# EE445L_Lab_7_Starter.net
KiCad netlist of a schematic drawn in EAGLE
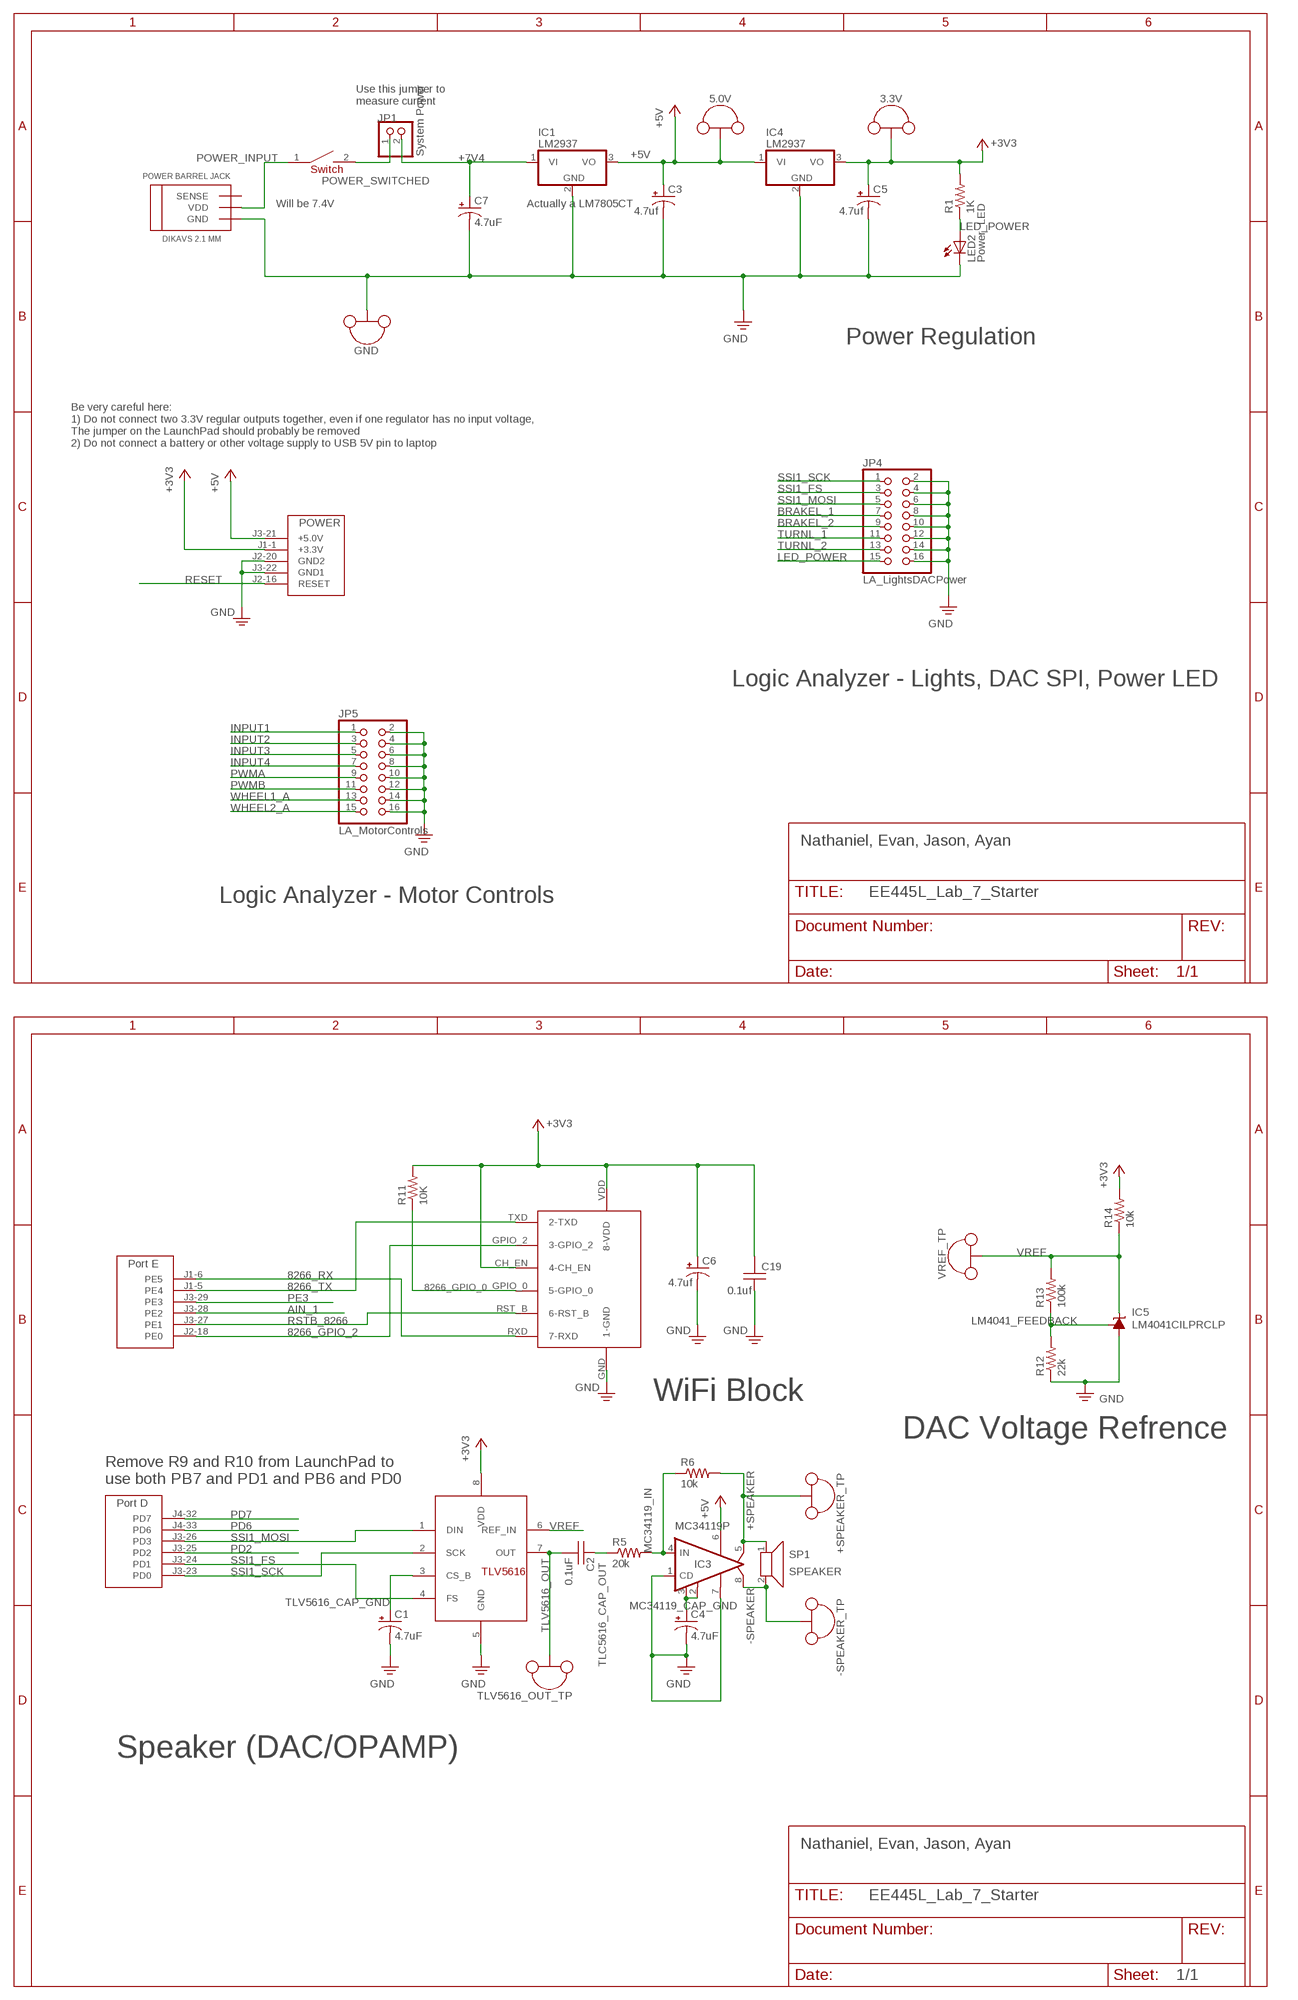
[diagram p0: schematic, sheet 1, part 1 of 2]
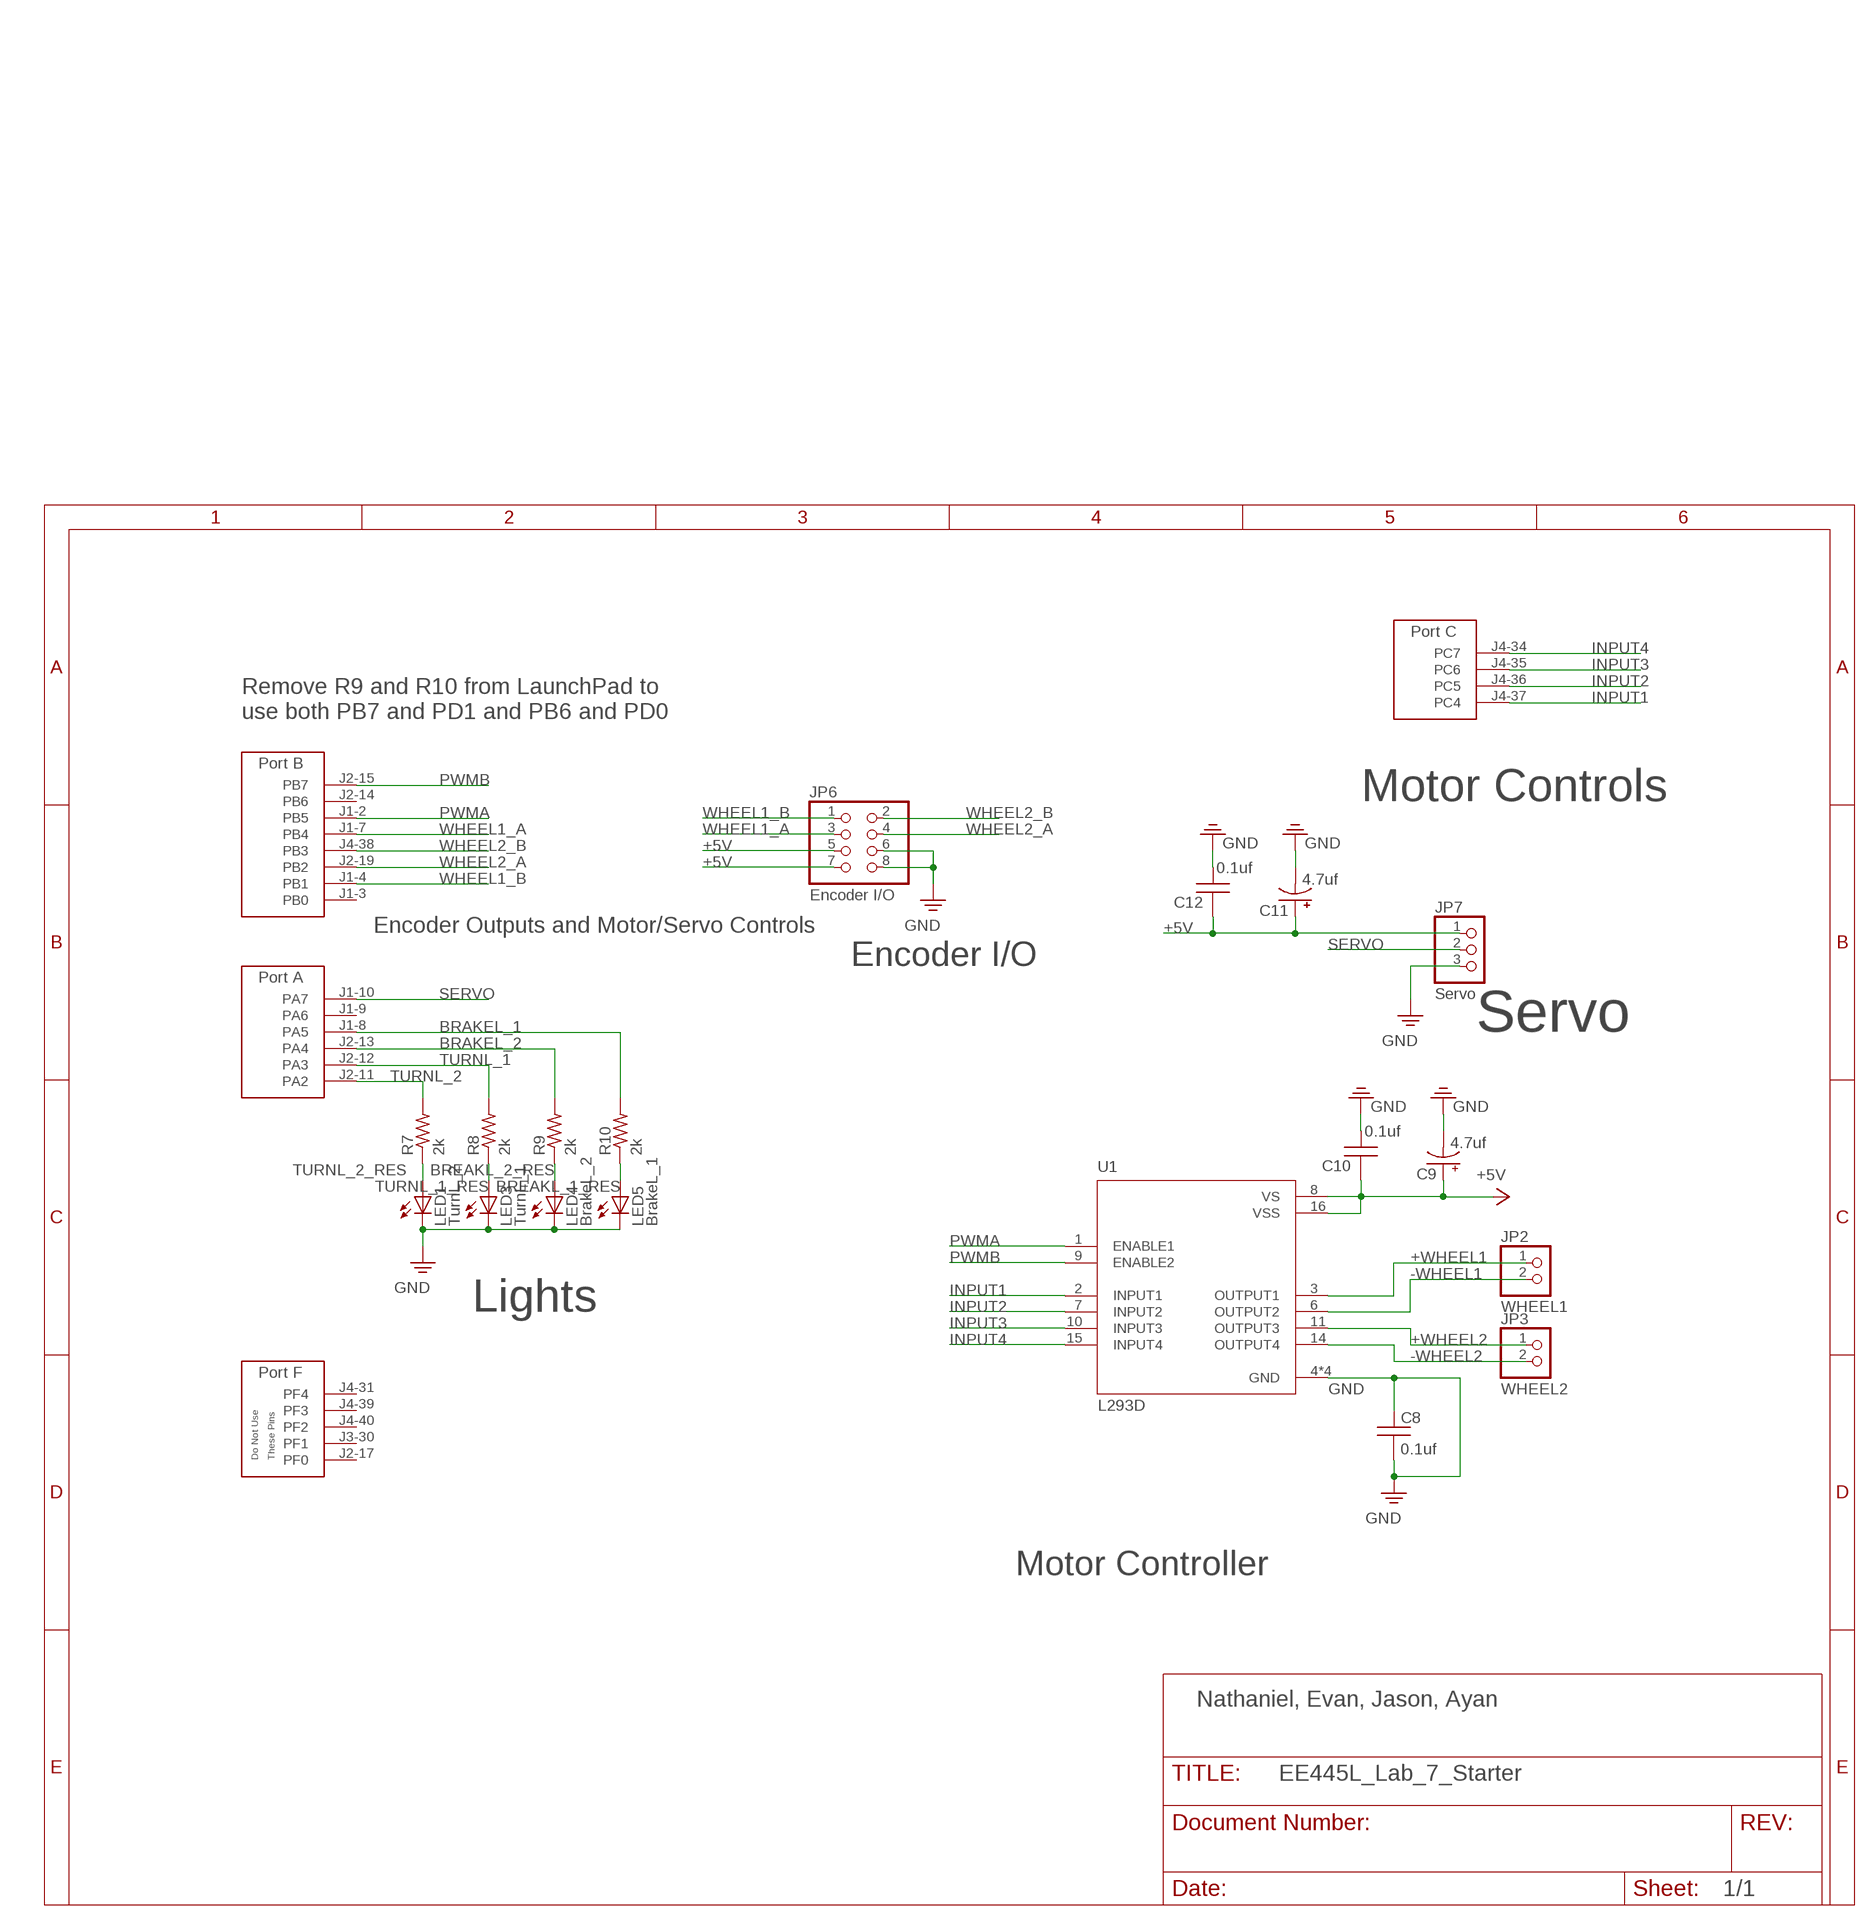
[diagram p1: schematic, sheet 1, part 2 of 2]

(export (version "E")
  (design (tool "Eeschema 10.0.6"))
  (components
    (comp (ref "+SPEAKER_TP")
      (value "TP_LOOP")
      (footprint "eagle-import:TP_LOOP")
      (libsource (lib "eagle-import") (part "TP_LOOP"))
    )
    (comp (ref "-SPEAKER_TP")
      (value "TP_LOOP")
      (footprint "eagle-import:TP_LOOP")
      (libsource (lib "eagle-import") (part "TP_LOOP"))
    )
    (comp (ref "3.3V")
      (value "TP_LOOP")
      (footprint "eagle-import:TP_LOOP")
      (libsource (lib "eagle-import") (part "TP_LOOP"))
    )
    (comp (ref "5.0V")
      (value "TP_LOOP")
      (footprint "eagle-import:TP_LOOP")
      (libsource (lib "eagle-import") (part "TP_LOOP"))
    )
    (comp (ref "C1")
      (value "4.7uF")
      (footprint "eagle-import:CAP200MILPOLARIZED")
      (libsource (lib "eagle-import") (part "CAPACITOR_POLARIZEDE5-6"))
    )
    (comp (ref "C2")
      (value "0.1uF")
      (footprint "eagle-import:CAP100MIL")
      (libsource (lib "eagle-import") (part "CAPACITOR025-024X044"))
    )
    (comp (ref "C3")
      (value "4.7uf")
      (footprint "eagle-import:CAP200MILPOLARIZED")
      (libsource (lib "eagle-import") (part "CAPACITOR_POLARIZEDE5-6"))
    )
    (comp (ref "C4")
      (value "4.7uF")
      (footprint "eagle-import:CAP200MILPOLARIZED")
      (libsource (lib "eagle-import") (part "CAPACITOR_POLARIZEDE5-6"))
    )
    (comp (ref "C5")
      (value "4.7uf")
      (footprint "eagle-import:CAP200MILPOLARIZED")
      (libsource (lib "eagle-import") (part "CAPACITOR_POLARIZEDE5-6"))
    )
    (comp (ref "C6")
      (value "4.7uf")
      (footprint "eagle-import:CAP200MILPOLARIZED")
      (libsource (lib "eagle-import") (part "CAPACITOR_POLARIZEDE5-6"))
    )
    (comp (ref "C7")
      (value "4.7uF")
      (footprint "eagle-import:CAP200MILPOLARIZED")
      (libsource (lib "eagle-import") (part "CAPACITOR_POLARIZEDE5-6"))
    )
    (comp (ref "C8")
      (value "0.1uf")
      (footprint "eagle-import:CAP100MIL")
      (libsource (lib "eagle-import") (part "CAPACITOR025-024X044"))
    )
    (comp (ref "C9")
      (value "4.7uf")
      (footprint "eagle-import:CAP200MILPOLARIZED")
      (libsource (lib "eagle-import") (part "CAPACITOR_POLARIZEDE5-6"))
    )
    (comp (ref "C10")
      (value "0.1uf")
      (footprint "eagle-import:CAP200MIL")
      (libsource (lib "eagle-import") (part "CAPACITOR050-024X044"))
    )
    (comp (ref "C11")
      (value "4.7uf")
      (footprint "eagle-import:CAP200MILPOLARIZED")
      (libsource (lib "eagle-import") (part "CAPACITOR_POLARIZEDE5-6"))
    )
    (comp (ref "C12")
      (value "0.1uf")
      (footprint "eagle-import:CAP200MIL")
      (libsource (lib "eagle-import") (part "CAPACITOR050-024X044"))
    )
    (comp (ref "C19")
      (value "0.1uf")
      (footprint "eagle-import:CAP200MIL")
      (libsource (lib "eagle-import") (part "CAPACITOR050-024X044"))
    )
    (comp (ref "GND")
      (value "TP_LOOP")
      (footprint "eagle-import:TP_LOOP")
      (libsource (lib "eagle-import") (part "TP_LOOP"))
    )
    (comp (ref "IC1")
      (value "LM2937")
      (footprint "eagle-import:TO220")
      (libsource (lib "eagle-import") (part "LM2937"))
    )
    (comp (ref "IC3")
      (value "MC34119P")
      (footprint "eagle-import:DIL08")
      (libsource (lib "eagle-import") (part "MC34119P"))
    )
    (comp (ref "IC4")
      (value "LM2937")
      (footprint "eagle-import:TO220")
      (libsource (lib "eagle-import") (part "LM2937"))
    )
    (comp (ref "IC5")
      (value "LM4041CILPRCLP")
      (footprint "eagle-import:LP_O-PBCY-W3")
      (fields (field (name "MPN") "LM4041CILP"))
      (libsource (lib "eagle-import") (part "LM4041CILPRLPC"))
    )
    (comp (ref "JP1")
      (value "System Power")
      (footprint "eagle-import:1X02")
      (libsource (lib "eagle-import") (part "PINHD-1X2"))
    )
    (comp (ref "JP2")
      (value "WHEEL1")
      (footprint "eagle-import:1X02")
      (libsource (lib "eagle-import") (part "PINHD-1X2"))
    )
    (comp (ref "JP3")
      (value "WHEEL2")
      (footprint "eagle-import:1X02")
      (libsource (lib "eagle-import") (part "PINHD-1X2"))
    )
    (comp (ref "JP4")
      (value "LA_LightsDACPower")
      (footprint "eagle-import:2X08")
      (libsource (lib "eagle-import") (part "PINHD-2X8"))
    )
    (comp (ref "JP5")
      (value "LA_MotorControls")
      (footprint "eagle-import:2X08")
      (libsource (lib "eagle-import") (part "PINHD-2X8"))
    )
    (comp (ref "JP6")
      (value "Encoder I/O")
      (footprint "eagle-import:2X04")
      (libsource (lib "eagle-import") (part "PINHD-2X4"))
    )
    (comp (ref "JP7")
      (value "Servo")
      (footprint "eagle-import:1X03")
      (libsource (lib "eagle-import") (part "PINHD-1X3"))
    )
    (comp (ref "LED1")
      (value "TurnL_2")
      (footprint "eagle-import:LED3MM")
      (libsource (lib "eagle-import") (part "LED3MM"))
    )
    (comp (ref "LED2")
      (value "Power_LED")
      (footprint "eagle-import:LED3MM")
      (libsource (lib "eagle-import") (part "LED3MM"))
    )
    (comp (ref "LED3")
      (value "TurnL_1")
      (footprint "eagle-import:LED3MM")
      (libsource (lib "eagle-import") (part "LED3MM"))
    )
    (comp (ref "LED4")
      (value "BrakeL_2")
      (footprint "eagle-import:LED3MM")
      (libsource (lib "eagle-import") (part "LED3MM"))
    )
    (comp (ref "LED5")
      (value "BrakeL_1")
      (footprint "eagle-import:LED3MM")
      (libsource (lib "eagle-import") (part "LED3MM"))
    )
    (comp (ref "R1")
      (value "1K")
      (footprint "eagle-import:RES200MIL")
      (libsource (lib "eagle-import") (part "RESISTOR0204/5"))
    )
    (comp (ref "R5")
      (value "20k")
      (footprint "eagle-import:RES200MIL")
      (libsource (lib "eagle-import") (part "RESISTOR0204/5"))
    )
    (comp (ref "R6")
      (value "10k")
      (footprint "eagle-import:RES200MIL")
      (libsource (lib "eagle-import") (part "RESISTOR0204/5"))
    )
    (comp (ref "R7")
      (value "2k")
      (footprint "eagle-import:RES200MIL")
      (libsource (lib "eagle-import") (part "RESISTOR0204/5"))
    )
    (comp (ref "R8")
      (value "2k")
      (footprint "eagle-import:RES200MIL")
      (libsource (lib "eagle-import") (part "RESISTOR0204/5"))
    )
    (comp (ref "R9")
      (value "2k")
      (footprint "eagle-import:RES200MIL")
      (libsource (lib "eagle-import") (part "RESISTOR0204/5"))
    )
    (comp (ref "R10")
      (value "2k")
      (footprint "eagle-import:RES200MIL")
      (libsource (lib "eagle-import") (part "RESISTOR0204/5"))
    )
    (comp (ref "R11")
      (value "10K")
      (footprint "eagle-import:RES300MIL")
      (libsource (lib "eagle-import") (part "RESISTOR0204/7"))
    )
    (comp (ref "R12")
      (value "22k")
      (footprint "eagle-import:RES300MIL")
      (libsource (lib "eagle-import") (part "RESISTOR0204/7"))
    )
    (comp (ref "R13")
      (value "100k")
      (footprint "eagle-import:RES300MIL")
      (libsource (lib "eagle-import") (part "RESISTOR0204/7"))
    )
    (comp (ref "R14")
      (value "10k")
      (footprint "eagle-import:RES300MIL")
      (libsource (lib "eagle-import") (part "RESISTOR0204/7"))
    )
    (comp (ref "SP1")
      (value "SPEAKER")
      (footprint "eagle-import:1X02")
      (libsource (lib "eagle-import") (part "SPEAKER"))
    )
    (comp (ref "TLV5616_OUT_TP")
      (value "TP_LOOP")
      (footprint "eagle-import:TP_LOOP")
      (libsource (lib "eagle-import") (part "TP_LOOP"))
    )
    (comp (ref "U$1")
      (value "TLV5616")
      (footprint "eagle-import:DIL08")
      (libsource (lib "eagle-import") (part "TLV5616"))
    )
    (comp (ref "U$2")
      (value "TM4C_BP")
      (footprint "eagle-import:TM4C_BOOSTER_PACK")
      (libsource (lib "eagle-import") (part "TM4C_BP"))
    )
    (comp (ref "U$3")
      (value "ESP_8266")
      (footprint "eagle-import:ESP8266")
      (libsource (lib "eagle-import") (part "ESP_8266"))
    )
    (comp (ref "U$4")
      (value "2.1MM_BARREL_JACK")
      (footprint "eagle-import:2.1M_BARREL_JACK")
      (libsource (lib "eagle-import") (part "2.1MM_BARREL_JACK"))
    )
    (comp (ref "U$6")
      (value "SW_POWER_100MIL")
      (footprint "eagle-import:SW_POWER")
      (libsource (lib "eagle-import") (part "SW_POWER_100MIL"))
    )
    (comp (ref "U1")
      (value "L293D")
      (footprint "eagle-import:DIP880W50P254L2000H510Q16")
      (fields (field (name "MF") "STMicroelectronics"))
      (libsource (lib "eagle-import") (part "L293D"))
    )
    (comp (ref "VREF_TP")
      (value "TP_LOOP")
      (footprint "eagle-import:TP_LOOP")
      (libsource (lib "eagle-import") (part "TP_LOOP"))
    )
  )
  (nets
    (net (code "1") (name "+3V3") (class "Default")
      (node (ref "3.3V") (pin "P$1") (pinfunction "TP_P$1") (pintype "bidirectional"))
      (node (ref "3.3V") (pin "P$2") (pinfunction "TP_P$2") (pintype "bidirectional"))
      (node (ref "C19") (pin "2") (pinfunction "2_2") (pintype "passive"))
      (node (ref "C5") (pin "+") (pinfunction "+_+") (pintype "passive"))
      (node (ref "C6") (pin "+") (pinfunction "+_+") (pintype "passive"))
      (node (ref "IC4") (pin "3") (pinfunction "VO_3") (pintype "passive"))
      (node (ref "R1") (pin "2") (pinfunction "2_2") (pintype "passive"))
      (node (ref "R11") (pin "2") (pinfunction "2_2") (pintype "passive"))
      (node (ref "R14") (pin "2") (pinfunction "2_2") (pintype "passive"))
      (node (ref "U$1") (pin "8") (pinfunction "VDD_8") (pintype "bidirectional"))
      (node (ref "U$2") (pin "J1-1") (pinfunction "+3.3V_J1-1") (pintype "bidirectional"))
      (node (ref "U$3") (pin "CH_EN") (pinfunction "4-CH_EN_CH_EN") (pintype "bidirectional"))
      (node (ref "U$3") (pin "VDD") (pinfunction "8-VDD_VDD") (pintype "bidirectional"))
    )
    (net (code "2") (name "+5V") (class "Default")
      (node (ref "5.0V") (pin "P$1") (pinfunction "TP_P$1") (pintype "bidirectional"))
      (node (ref "5.0V") (pin "P$2") (pinfunction "TP_P$2") (pintype "bidirectional"))
      (node (ref "C10") (pin "2") (pinfunction "2_2") (pintype "passive"))
      (node (ref "C11") (pin "+") (pinfunction "+_+") (pintype "passive"))
      (node (ref "C12") (pin "2") (pinfunction "2_2") (pintype "passive"))
      (node (ref "C3") (pin "+") (pinfunction "+_+") (pintype "passive"))
      (node (ref "C9") (pin "+") (pinfunction "+_+") (pintype "passive"))
      (node (ref "IC1") (pin "3") (pinfunction "VO_3") (pintype "passive"))
      (node (ref "IC3") (pin "6") (pinfunction "VCC_6") (pintype "power_in"))
      (node (ref "IC4") (pin "1") (pinfunction "VI_1") (pintype "input"))
      (node (ref "JP6") (pin "5") (pinfunction "5_5") (pintype "passive"))
      (node (ref "JP6") (pin "7") (pinfunction "7_7") (pintype "passive"))
      (node (ref "JP7") (pin "1") (pinfunction "1_1") (pintype "passive"))
      (node (ref "U$2") (pin "J3-21") (pinfunction "+5.0V_J3-21") (pintype "bidirectional"))
      (node (ref "U1") (pin "16") (pinfunction "VSS_16") (pintype "power_in"))
      (node (ref "U1") (pin "8") (pinfunction "VS_8") (pintype "power_in"))
    )
    (net (code "3") (name "/+7V4") (class "Default")
      (node (ref "C7") (pin "+") (pinfunction "+_+") (pintype "passive"))
      (node (ref "IC1") (pin "1") (pinfunction "VI_1") (pintype "input"))
      (node (ref "JP1") (pin "2") (pinfunction "2_2") (pintype "passive"))
    )
    (net (code "4") (name "/+SPEAKER") (class "Default")
      (node (ref "+SPEAKER_TP") (pin "P$1") (pinfunction "TP_P$1") (pintype "bidirectional"))
      (node (ref "+SPEAKER_TP") (pin "P$2") (pinfunction "TP_P$2") (pintype "bidirectional"))
      (node (ref "IC3") (pin "5") (pinfunction "VO1_5") (pintype "output"))
      (node (ref "R6") (pin "2") (pinfunction "2_2") (pintype "passive"))
      (node (ref "SP1") (pin "1") (pinfunction "1_1") (pintype "passive"))
    )
    (net (code "5") (name "/+WHEEL1") (class "Default")
      (node (ref "JP2") (pin "1") (pinfunction "1_1") (pintype "passive"))
      (node (ref "U1") (pin "3") (pinfunction "OUTPUT1_3") (pintype "output"))
    )
    (net (code "6") (name "/+WHEEL2") (class "Default")
      (node (ref "JP3") (pin "1") (pinfunction "1_1") (pintype "passive"))
      (node (ref "U1") (pin "11") (pinfunction "OUTPUT3_11") (pintype "output"))
    )
    (net (code "7") (name "/-SPEAKER") (class "Default")
      (node (ref "-SPEAKER_TP") (pin "P$1") (pinfunction "TP_P$1") (pintype "bidirectional"))
      (node (ref "-SPEAKER_TP") (pin "P$2") (pinfunction "TP_P$2") (pintype "bidirectional"))
      (node (ref "IC3") (pin "8") (pinfunction "VO2_8") (pintype "output"))
      (node (ref "SP1") (pin "2") (pinfunction "2_2") (pintype "passive"))
    )
    (net (code "8") (name "/-WHEEL1") (class "Default")
      (node (ref "JP2") (pin "2") (pinfunction "2_2") (pintype "passive"))
      (node (ref "U1") (pin "6") (pinfunction "OUTPUT2_6") (pintype "output"))
    )
    (net (code "9") (name "/-WHEEL2") (class "Default")
      (node (ref "JP3") (pin "2") (pinfunction "2_2") (pintype "passive"))
      (node (ref "U1") (pin "14") (pinfunction "OUTPUT4_14") (pintype "output"))
    )
    (net (code "10") (name "/8266_GPIO_0") (class "Default")
      (node (ref "R11") (pin "1") (pinfunction "1_1") (pintype "passive"))
      (node (ref "U$3") (pin "GPIO_0") (pinfunction "5-GPIO_0_GPIO_0") (pintype "bidirectional"))
    )
    (net (code "11") (name "/8266_GPIO_2") (class "Default")
      (node (ref "U$2") (pin "J2-18") (pinfunction "PE0_J2-18") (pintype "bidirectional"))
      (node (ref "U$3") (pin "GPIO_2") (pinfunction "3-GPIO_2_GPIO_2") (pintype "bidirectional"))
    )
    (net (code "12") (name "/8266_RX") (class "Default")
      (node (ref "U$2") (pin "J1-6") (pinfunction "PE5_J1-6") (pintype "bidirectional"))
      (node (ref "U$3") (pin "RXD") (pinfunction "7-RXD_RXD") (pintype "bidirectional"))
    )
    (net (code "13") (name "/8266_TX") (class "Default")
      (node (ref "U$2") (pin "J1-5") (pinfunction "PE4_J1-5") (pintype "bidirectional"))
      (node (ref "U$3") (pin "TXD") (pinfunction "2-TXD_TXD") (pintype "bidirectional"))
    )
    (net (code "14") (name "/AIN_1") (class "Default")
      (node (ref "U$2") (pin "J3-28") (pinfunction "PE2_J3-28") (pintype "bidirectional"))
    )
    (net (code "15") (name "/BRAKEL_1") (class "Default")
      (node (ref "JP4") (pin "7") (pinfunction "7_7") (pintype "passive"))
      (node (ref "R10") (pin "2") (pinfunction "2_2") (pintype "passive"))
      (node (ref "U$2") (pin "J1-8") (pinfunction "PA5_J1-8") (pintype "bidirectional"))
    )
    (net (code "16") (name "/BRAKEL_2") (class "Default")
      (node (ref "JP4") (pin "9") (pinfunction "9_9") (pintype "passive"))
      (node (ref "R9") (pin "2") (pinfunction "2_2") (pintype "passive"))
      (node (ref "U$2") (pin "J2-13") (pinfunction "PA4_J2-13") (pintype "bidirectional"))
    )
    (net (code "17") (name "/BREAKL_1_RES") (class "Default")
      (node (ref "LED5") (pin "A") (pinfunction "A_A") (pintype "passive"))
      (node (ref "R10") (pin "1") (pinfunction "1_1") (pintype "passive"))
    )
    (net (code "18") (name "/BREAKL_2_RES") (class "Default")
      (node (ref "LED4") (pin "A") (pinfunction "A_A") (pintype "passive"))
      (node (ref "R9") (pin "1") (pinfunction "1_1") (pintype "passive"))
    )
    (net (code "19") (name "/INPUT1") (class "Default")
      (node (ref "JP5") (pin "1") (pinfunction "1_1") (pintype "passive"))
      (node (ref "U$2") (pin "J4-37") (pinfunction "PC4_J4-37") (pintype "bidirectional"))
      (node (ref "U1") (pin "2") (pinfunction "INPUT1_2") (pintype "input"))
    )
    (net (code "20") (name "/INPUT2") (class "Default")
      (node (ref "JP5") (pin "3") (pinfunction "3_3") (pintype "passive"))
      (node (ref "U$2") (pin "J4-36") (pinfunction "PC5_J4-36") (pintype "bidirectional"))
      (node (ref "U1") (pin "7") (pinfunction "INPUT2_7") (pintype "input"))
    )
    (net (code "21") (name "/INPUT3") (class "Default")
      (node (ref "JP5") (pin "5") (pinfunction "5_5") (pintype "passive"))
      (node (ref "U$2") (pin "J4-35") (pinfunction "PC6_J4-35") (pintype "bidirectional"))
      (node (ref "U1") (pin "10") (pinfunction "INPUT3_10") (pintype "input"))
    )
    (net (code "22") (name "/INPUT4") (class "Default")
      (node (ref "JP5") (pin "7") (pinfunction "7_7") (pintype "passive"))
      (node (ref "U$2") (pin "J4-34") (pinfunction "PC7_J4-34") (pintype "bidirectional"))
      (node (ref "U1") (pin "15") (pinfunction "INPUT4_15") (pintype "input"))
    )
    (net (code "23") (name "/LED_POWER") (class "Default")
      (node (ref "JP4") (pin "15") (pinfunction "15_15") (pintype "passive"))
      (node (ref "LED2") (pin "A") (pinfunction "A_A") (pintype "passive"))
      (node (ref "R1") (pin "1") (pinfunction "1_1") (pintype "passive"))
    )
    (net (code "24") (name "/LM4041_FEEDBACK") (class "Default")
      (node (ref "IC5") (pin "1") (pinfunction "FB_1") (pintype "passive"))
      (node (ref "R12") (pin "2") (pinfunction "2_2") (pintype "passive"))
      (node (ref "R13") (pin "1") (pinfunction "1_1") (pintype "passive"))
    )
    (net (code "25") (name "/MC34119_CAP_GND") (class "Default")
      (node (ref "C4") (pin "+") (pinfunction "+_+") (pintype "passive"))
      (node (ref "IC3") (pin "2") (pinfunction "FC2_2") (pintype "passive"))
      (node (ref "IC3") (pin "3") (pinfunction "FC1_3") (pintype "passive"))
    )
    (net (code "26") (name "/MC34119_IN") (class "Default")
      (node (ref "IC3") (pin "4") (pinfunction "IN_4") (pintype "input"))
      (node (ref "R5") (pin "2") (pinfunction "2_2") (pintype "passive"))
      (node (ref "R6") (pin "1") (pinfunction "1_1") (pintype "passive"))
    )
    (net (code "27") (name "/PD2") (class "Default")
      (node (ref "U$2") (pin "J3-25") (pinfunction "PD2_J3-25") (pintype "bidirectional"))
    )
    (net (code "28") (name "/PD6") (class "Default")
      (node (ref "U$2") (pin "J4-33") (pinfunction "PD6_J4-33") (pintype "bidirectional"))
    )
    (net (code "29") (name "/PD7") (class "Default")
      (node (ref "U$2") (pin "J4-32") (pinfunction "PD7_J4-32") (pintype "bidirectional"))
    )
    (net (code "30") (name "/PE3") (class "Default")
      (node (ref "U$2") (pin "J3-29") (pinfunction "PE3_J3-29") (pintype "bidirectional"))
    )
    (net (code "31") (name "/POWER_INPUT") (class "Default")
      (node (ref "U$4") (pin "VDD") (pinfunction "VDD_VDD") (pintype "bidirectional"))
      (node (ref "U$6") (pin "1") (pinfunction "P$1_1") (pintype "bidirectional"))
    )
    (net (code "32") (name "/POWER_SWITCHED") (class "Default")
      (node (ref "JP1") (pin "1") (pinfunction "1_1") (pintype "passive"))
      (node (ref "U$6") (pin "2") (pinfunction "P$2_2") (pintype "bidirectional"))
    )
    (net (code "33") (name "/PWMA") (class "Default")
      (node (ref "JP5") (pin "9") (pinfunction "9_9") (pintype "passive"))
      (node (ref "U$2") (pin "J1-2") (pinfunction "PB5_J1-2") (pintype "bidirectional"))
      (node (ref "U1") (pin "1") (pinfunction "ENABLE1_1") (pintype "input"))
    )
    (net (code "34") (name "/PWMB") (class "Default")
      (node (ref "JP5") (pin "11") (pinfunction "11_11") (pintype "passive"))
      (node (ref "U$2") (pin "J2-15") (pinfunction "PB7_J2-15") (pintype "bidirectional"))
      (node (ref "U1") (pin "9") (pinfunction "ENABLE2_9") (pintype "input"))
    )
    (net (code "35") (name "/RESET") (class "Default")
      (node (ref "U$2") (pin "J2-16") (pinfunction "RESET_J2-16") (pintype "bidirectional"))
    )
    (net (code "36") (name "/RSTB_8266") (class "Default")
      (node (ref "U$2") (pin "J3-27") (pinfunction "PE1_J3-27") (pintype "bidirectional"))
      (node (ref "U$3") (pin "RST_B") (pinfunction "6-RST_B_RST_B") (pintype "bidirectional"))
    )
    (net (code "37") (name "/SERVO") (class "Default")
      (node (ref "JP7") (pin "2") (pinfunction "2_2") (pintype "passive"))
      (node (ref "U$2") (pin "J1-10") (pinfunction "PA7_J1-10") (pintype "bidirectional"))
    )
    (net (code "38") (name "/SSI1_FS") (class "Default")
      (node (ref "JP4") (pin "3") (pinfunction "3_3") (pintype "passive"))
      (node (ref "U$1") (pin "4") (pinfunction "FS_4") (pintype "bidirectional"))
      (node (ref "U$2") (pin "J3-24") (pinfunction "PD1_J3-24") (pintype "bidirectional"))
    )
    (net (code "39") (name "/SSI1_MOSI") (class "Default")
      (node (ref "JP4") (pin "5") (pinfunction "5_5") (pintype "passive"))
      (node (ref "U$1") (pin "1") (pinfunction "DIN_1") (pintype "bidirectional"))
      (node (ref "U$2") (pin "J3-26") (pinfunction "PD3_J3-26") (pintype "bidirectional"))
    )
    (net (code "40") (name "/SSI1_SCK") (class "Default")
      (node (ref "JP4") (pin "1") (pinfunction "1_1") (pintype "passive"))
      (node (ref "U$1") (pin "2") (pinfunction "SCK_2") (pintype "bidirectional"))
      (node (ref "U$2") (pin "J3-23") (pinfunction "PD0_J3-23") (pintype "bidirectional"))
    )
    (net (code "41") (name "/TLC5616_CAP_OUT") (class "Default")
      (node (ref "C2") (pin "1") (pinfunction "1_1") (pintype "passive"))
      (node (ref "R5") (pin "1") (pinfunction "1_1") (pintype "passive"))
    )
    (net (code "42") (name "/TLV5616_CAP_GND") (class "Default")
      (node (ref "C1") (pin "+") (pinfunction "+_+") (pintype "passive"))
      (node (ref "U$1") (pin "3") (pinfunction "CS_B_3") (pintype "bidirectional"))
    )
    (net (code "43") (name "/TLV5616_OUT") (class "Default")
      (node (ref "C2") (pin "2") (pinfunction "2_2") (pintype "passive"))
      (node (ref "TLV5616_OUT_TP") (pin "P$1") (pinfunction "TP_P$1") (pintype "bidirectional"))
      (node (ref "TLV5616_OUT_TP") (pin "P$2") (pinfunction "TP_P$2") (pintype "bidirectional"))
      (node (ref "U$1") (pin "7") (pinfunction "OUT_7") (pintype "bidirectional"))
    )
    (net (code "44") (name "/TURNL_1") (class "Default")
      (node (ref "JP4") (pin "11") (pinfunction "11_11") (pintype "passive"))
      (node (ref "R8") (pin "2") (pinfunction "2_2") (pintype "passive"))
      (node (ref "U$2") (pin "J2-12") (pinfunction "PA3_J2-12") (pintype "bidirectional"))
    )
    (net (code "45") (name "/TURNL_1_RES") (class "Default")
      (node (ref "LED3") (pin "A") (pinfunction "A_A") (pintype "passive"))
      (node (ref "R8") (pin "1") (pinfunction "1_1") (pintype "passive"))
    )
    (net (code "46") (name "/TURNL_2") (class "Default")
      (node (ref "JP4") (pin "13") (pinfunction "13_13") (pintype "passive"))
      (node (ref "R7") (pin "2") (pinfunction "2_2") (pintype "passive"))
      (node (ref "U$2") (pin "J2-11") (pinfunction "PA2_J2-11") (pintype "bidirectional"))
    )
    (net (code "47") (name "/TURNL_2_RES") (class "Default")
      (node (ref "LED1") (pin "A") (pinfunction "A_A") (pintype "passive"))
      (node (ref "R7") (pin "1") (pinfunction "1_1") (pintype "passive"))
    )
    (net (code "48") (name "/VREF") (class "Default")
      (node (ref "IC5") (pin "2") (pinfunction "C_2") (pintype "passive"))
      (node (ref "R13") (pin "2") (pinfunction "2_2") (pintype "passive"))
      (node (ref "R14") (pin "1") (pinfunction "1_1") (pintype "passive"))
      (node (ref "U$1") (pin "6") (pinfunction "REF_IN_6") (pintype "bidirectional"))
      (node (ref "VREF_TP") (pin "P$1") (pinfunction "TP_P$1") (pintype "bidirectional"))
      (node (ref "VREF_TP") (pin "P$2") (pinfunction "TP_P$2") (pintype "bidirectional"))
    )
    (net (code "49") (name "/WHEEL1_A") (class "Default")
      (node (ref "JP5") (pin "13") (pinfunction "13_13") (pintype "passive"))
      (node (ref "JP6") (pin "3") (pinfunction "3_3") (pintype "passive"))
      (node (ref "U$2") (pin "J1-7") (pinfunction "PB4_J1-7") (pintype "bidirectional"))
    )
    (net (code "50") (name "/WHEEL1_B") (class "Default")
      (node (ref "JP6") (pin "1") (pinfunction "1_1") (pintype "passive"))
      (node (ref "U$2") (pin "J1-4") (pinfunction "PB1_J1-4") (pintype "bidirectional"))
    )
    (net (code "51") (name "/WHEEL2_A") (class "Default")
      (node (ref "JP5") (pin "15") (pinfunction "15_15") (pintype "passive"))
      (node (ref "JP6") (pin "4") (pinfunction "4_4") (pintype "passive"))
      (node (ref "U$2") (pin "J2-19") (pinfunction "PB2_J2-19") (pintype "bidirectional"))
    )
    (net (code "52") (name "/WHEEL2_B") (class "Default")
      (node (ref "JP6") (pin "2") (pinfunction "2_2") (pintype "passive"))
      (node (ref "U$2") (pin "J4-38") (pinfunction "PB3_J4-38") (pintype "bidirectional"))
    )
    (net (code "53") (name "GND") (class "Default")
      (node (ref "C1") (pin "-") (pinfunction "-_-") (pintype "passive"))
      (node (ref "C10") (pin "1") (pinfunction "1_1") (pintype "passive"))
      (node (ref "C11") (pin "-") (pinfunction "-_-") (pintype "passive"))
      (node (ref "C12") (pin "1") (pinfunction "1_1") (pintype "passive"))
      (node (ref "C19") (pin "1") (pinfunction "1_1") (pintype "passive"))
      (node (ref "C3") (pin "-") (pinfunction "-_-") (pintype "passive"))
      (node (ref "C4") (pin "-") (pinfunction "-_-") (pintype "passive"))
      (node (ref "C5") (pin "-") (pinfunction "-_-") (pintype "passive"))
      (node (ref "C6") (pin "-") (pinfunction "-_-") (pintype "passive"))
      (node (ref "C7") (pin "-") (pinfunction "-_-") (pintype "passive"))
      (node (ref "C8") (pin "1") (pinfunction "1_1") (pintype "passive"))
      (node (ref "C8") (pin "2") (pinfunction "2_2") (pintype "passive"))
      (node (ref "C9") (pin "-") (pinfunction "-_-") (pintype "passive"))
      (node (ref "GND") (pin "P$1") (pinfunction "TP_P$1") (pintype "bidirectional"))
      (node (ref "GND") (pin "P$2") (pinfunction "TP_P$2") (pintype "bidirectional"))
      (node (ref "IC1") (pin "2") (pinfunction "GND_2") (pintype "passive"))
      (node (ref "IC3") (pin "1") (pinfunction "CD_1") (pintype "passive"))
      (node (ref "IC3") (pin "7") (pinfunction "GND_7") (pintype "power_in"))
      (node (ref "IC4") (pin "2") (pinfunction "GND_2") (pintype "passive"))
      (node (ref "IC5") (pin "3") (pinfunction "A_3") (pintype "passive"))
      (node (ref "JP4") (pin "10") (pinfunction "10_10") (pintype "passive"))
      (node (ref "JP4") (pin "12") (pinfunction "12_12") (pintype "passive"))
      (node (ref "JP4") (pin "14") (pinfunction "14_14") (pintype "passive"))
      (node (ref "JP4") (pin "16") (pinfunction "16_16") (pintype "passive"))
      (node (ref "JP4") (pin "2") (pinfunction "2_2") (pintype "passive"))
      (node (ref "JP4") (pin "4") (pinfunction "4_4") (pintype "passive"))
      (node (ref "JP4") (pin "6") (pinfunction "6_6") (pintype "passive"))
      (node (ref "JP4") (pin "8") (pinfunction "8_8") (pintype "passive"))
      (node (ref "JP5") (pin "10") (pinfunction "10_10") (pintype "passive"))
      (node (ref "JP5") (pin "12") (pinfunction "12_12") (pintype "passive"))
      (node (ref "JP5") (pin "14") (pinfunction "14_14") (pintype "passive"))
      (node (ref "JP5") (pin "16") (pinfunction "16_16") (pintype "passive"))
      (node (ref "JP5") (pin "2") (pinfunction "2_2") (pintype "passive"))
      (node (ref "JP5") (pin "4") (pinfunction "4_4") (pintype "passive"))
      (node (ref "JP5") (pin "6") (pinfunction "6_6") (pintype "passive"))
      (node (ref "JP5") (pin "8") (pinfunction "8_8") (pintype "passive"))
      (node (ref "JP6") (pin "6") (pinfunction "6_6") (pintype "passive"))
      (node (ref "JP6") (pin "8") (pinfunction "8_8") (pintype "passive"))
      (node (ref "JP7") (pin "3") (pinfunction "3_3") (pintype "passive"))
      (node (ref "LED1") (pin "K") (pinfunction "C_K") (pintype "passive"))
      (node (ref "LED2") (pin "K") (pinfunction "C_K") (pintype "passive"))
      (node (ref "LED3") (pin "K") (pinfunction "C_K") (pintype "passive"))
      (node (ref "LED4") (pin "K") (pinfunction "C_K") (pintype "passive"))
      (node (ref "LED5") (pin "K") (pinfunction "C_K") (pintype "passive"))
      (node (ref "R12") (pin "1") (pinfunction "1_1") (pintype "passive"))
      (node (ref "U$1") (pin "5") (pinfunction "GND_5") (pintype "bidirectional"))
      (node (ref "U$2") (pin "J2-20") (pinfunction "GND2_J2-20") (pintype "bidirectional"))
      (node (ref "U$2") (pin "J3-22") (pinfunction "GND1_J3-22") (pintype "bidirectional"))
      (node (ref "U$3") (pin "GND") (pinfunction "1-GND_GND") (pintype "bidirectional"))
      (node (ref "U$4") (pin "GND") (pinfunction "GND_GND") (pintype "bidirectional"))
      (node (ref "U1") (pin "12") (pinfunction "GND_12") (pintype "power_in"))
      (node (ref "U1") (pin "13") (pinfunction "GND_13") (pintype "power_in"))
      (node (ref "U1") (pin "4") (pinfunction "GND_4") (pintype "power_in"))
      (node (ref "U1") (pin "5") (pinfunction "GND_5") (pintype "power_in"))
    )
    (net (code "54") (name "unconnected-(U$2A-PA6-PadJ1-9)") (class "Default")
      (node (ref "U$2") (pin "J1-9") (pinfunction "PA6_J1-9") (pintype "bidirectional"))
    )
    (net (code "55") (name "unconnected-(U$2B-PB0-PadJ1-3)") (class "Default")
      (node (ref "U$2") (pin "J1-3") (pinfunction "PB0_J1-3") (pintype "bidirectional"))
    )
    (net (code "56") (name "unconnected-(U$2B-PB6-PadJ2-14)") (class "Default")
      (node (ref "U$2") (pin "J2-14") (pinfunction "PB6_J2-14") (pintype "bidirectional"))
    )
    (net (code "57") (name "unconnected-(U$2F-PF0-PadJ2-17)") (class "Default")
      (node (ref "U$2") (pin "J2-17") (pinfunction "PF0_J2-17") (pintype "bidirectional"))
    )
    (net (code "58") (name "unconnected-(U$2F-PF1-PadJ3-30)") (class "Default")
      (node (ref "U$2") (pin "J3-30") (pinfunction "PF1_J3-30") (pintype "bidirectional"))
    )
    (net (code "59") (name "unconnected-(U$2F-PF2-PadJ4-40)") (class "Default")
      (node (ref "U$2") (pin "J4-40") (pinfunction "PF2_J4-40") (pintype "bidirectional"))
    )
    (net (code "60") (name "unconnected-(U$2F-PF3-PadJ4-39)") (class "Default")
      (node (ref "U$2") (pin "J4-39") (pinfunction "PF3_J4-39") (pintype "bidirectional"))
    )
    (net (code "61") (name "unconnected-(U$2F-PF4-PadJ4-31)") (class "Default")
      (node (ref "U$2") (pin "J4-31") (pinfunction "PF4_J4-31") (pintype "bidirectional"))
    )
    (net (code "62") (name "unconnected-(U$4-PadSENSE)") (class "Default")
      (node (ref "U$4") (pin "SENSE") (pinfunction "SENSE_SENSE") (pintype "bidirectional"))
    )
  )
)
